# ab.net
KiCad netlist of a schematic drawn in EAGLE
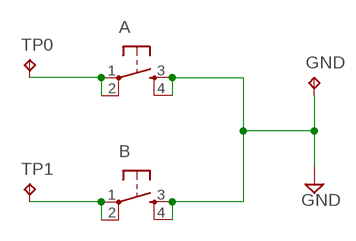
[diagram p0: schematic, sheet 1]

(export (version "E")
  (design (tool "Eeschema 10.0.6"))
  (components
    (comp (ref "A")
      (value "BUTTON")
      (footprint "eagle-import:SMD_BUTTON")
      (fields (field (name "MPN") "B3F-1000"))
      (libsource (lib "eagle-import") (part "BUTTON"))
    )
    (comp (ref "B")
      (value "BUTTON")
      (footprint "eagle-import:SMD_BUTTON")
      (fields (field (name "MPN") "B3F-1000"))
      (libsource (lib "eagle-import") (part "BUTTON"))
    )
    (comp (ref "GND")
      (value "TPPAD1-13")
      (footprint "eagle-import:P1-13")
      (libsource (lib "eagle-import") (part "TPPAD1-13"))
    )
    (comp (ref "TP0")
      (value "TPPAD1-13")
      (footprint "eagle-import:P1-13")
      (libsource (lib "eagle-import") (part "TPPAD1-13"))
    )
    (comp (ref "TP1")
      (value "TPPAD1-13")
      (footprint "eagle-import:P1-13")
      (libsource (lib "eagle-import") (part "TPPAD1-13"))
    )
  )
  (nets
    (net (code "1") (name "GND") (class "Default")
      (node (ref "A") (pin "3") (pinfunction "S_3") (pintype "passive"))
      (node (ref "A") (pin "4") (pinfunction "S1_4") (pintype "passive"))
      (node (ref "B") (pin "3") (pinfunction "S_3") (pintype "passive"))
      (node (ref "B") (pin "4") (pinfunction "S1_4") (pintype "passive"))
      (node (ref "GND") (pin "TP") (pinfunction "TP_TP") (pintype "input"))
    )
    (net (code "2") (name "Net-(A-P)") (class "Default")
      (node (ref "A") (pin "1") (pinfunction "P_1") (pintype "passive"))
      (node (ref "A") (pin "2") (pinfunction "P1_2") (pintype "passive"))
      (node (ref "TP0") (pin "TP") (pinfunction "TP_TP") (pintype "input"))
    )
    (net (code "3") (name "Net-(B-P)") (class "Default")
      (node (ref "B") (pin "1") (pinfunction "P_1") (pintype "passive"))
      (node (ref "B") (pin "2") (pinfunction "P1_2") (pintype "passive"))
      (node (ref "TP1") (pin "TP") (pinfunction "TP_TP") (pintype "input"))
    )
  )
)
